# TPSM846C23_template.net
KiCad netlist of a schematic drawn in Altium Designer
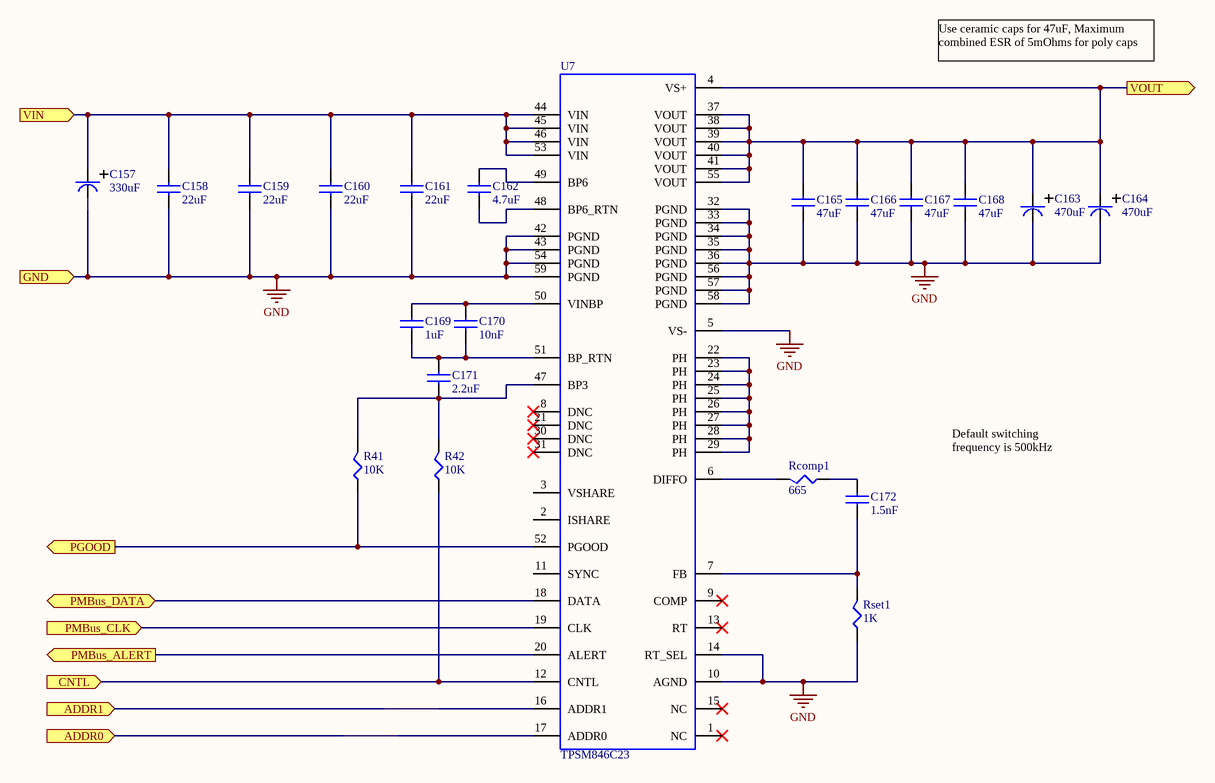
[diagram p0: TPSM846C23_template.SchDoc]

(export (version "E")
  (design (tool "Eeschema 10.0.6"))
  (components
    (comp (ref "C157")
      (value "CAP_POLY_330uF_25V")
      (footprint "CAPAE110103X127M")
      (description "SML-D12U1WT86TR-ND")
      (fields
        (field (name "MANUFACTURER") "Panasonic")
        (field (name "MANUFACTURER PART NUMBER") "25SVF330M")
        (field (name "CAPACITANCE") "330uF")
      )
      (libsource (lib "my_schsymbols") (part "CAP_POLY_330uF_25V"))
    )
    (comp (ref "C158")
      (value "CAP_22uF_1812_25V")
      (footprint "CAPC4532X28N")
      (description "CAP CER 22UF 25V X7R 1812")
      (fields
        (field (name "MANUFACTURER") "TDK")
        (field (name "MANUFACTURER PART NUMBER") "C4532X7R1E226M250KC")
        (field (name "CAPACITANCE") "22uF")
      )
      (libsource (lib "my_schsymbols") (part "CAP_22uF_1812_25V"))
    )
    (comp (ref "C159")
      (value "CAP_22uF_1812_25V")
      (footprint "CAPC4532X28N")
      (description "CAP CER 22UF 25V X7R 1812")
      (fields
        (field (name "MANUFACTURER") "TDK")
        (field (name "MANUFACTURER PART NUMBER") "C4532X7R1E226M250KC")
        (field (name "CAPACITANCE") "22uF")
      )
      (libsource (lib "my_schsymbols") (part "CAP_22uF_1812_25V"))
    )
    (comp (ref "C160")
      (value "CAP_22uF_1812_25V")
      (footprint "CAPC4532X28N")
      (description "CAP CER 22UF 25V X7R 1812")
      (fields
        (field (name "MANUFACTURER") "TDK")
        (field (name "MANUFACTURER PART NUMBER") "C4532X7R1E226M250KC")
        (field (name "CAPACITANCE") "22uF")
      )
      (libsource (lib "my_schsymbols") (part "CAP_22uF_1812_25V"))
    )
    (comp (ref "C161")
      (value "CAP_22uF_1812_25V")
      (footprint "CAPC4532X28N")
      (description "CAP CER 22UF 25V X7R 1812")
      (fields
        (field (name "MANUFACTURER") "TDK")
        (field (name "MANUFACTURER PART NUMBER") "C4532X7R1E226M250KC")
        (field (name "CAPACITANCE") "22uF")
      )
      (libsource (lib "my_schsymbols") (part "CAP_22uF_1812_25V"))
    )
    (comp (ref "C162")
      (value "CAP_4.7uF_0805_25V")
      (footprint "CAPC2012X14N")
      (description "Cap Ceramic 4.7uF 25V X5R 10% SMD 0805 85C Cardboard T/R")
      (fields
        (field (name "MANUFACTURER") "Samsung")
        (field (name "MANUFACTURER PART NUMBER") "CL21A475KACLRNC")
        (field (name "CAPACITANCE") "4.7uF")
      )
      (libsource (lib "CGRA_schlib") (part "CAP_4.7uF_0805_25V"))
    )
    (comp (ref "C163")
      (value "CAP_POLY_470uF_16V")
      (footprint "CAPAE110103X127M")
      (description "CAP POLYMER 470UF 20% 16V SMD")
      (fields
        (field (name "MANUFACTURER") "Panasonic")
        (field (name "MANUFACTURER PART NUMBER") "25SVF330M")
        (field (name "CAPACITANCE") "470uF")
      )
      (libsource (lib "my_schsymbols") (part "CAP_POLY_470uF_16V"))
    )
    (comp (ref "C164")
      (value "CAP_POLY_470uF_16V")
      (footprint "CAPAE110103X127M")
      (description "CAP POLYMER 470UF 20% 16V SMD")
      (fields
        (field (name "MANUFACTURER") "Panasonic")
        (field (name "MANUFACTURER PART NUMBER") "25SVF330M")
        (field (name "CAPACITANCE") "470uF")
      )
      (libsource (lib "my_schsymbols") (part "CAP_POLY_470uF_16V"))
    )
    (comp (ref "C165")
      (value "CAP_47uF_0805_10V")
      (footprint "CAPC2012X14N")
      (description "Cap Ceramic 47uF 10V X5R 20% SMD 0805 85C Embossed T/R")
      (fields
        (field (name "MANUFACTURER") "Murata")
        (field (name "MANUFACTURER PART NUMBER") "GRM21BR61A476ME15L")
        (field (name "CAPACITANCE") "47uF")
      )
      (libsource (lib "CGRA_schlib") (part "CAP_47uF_0805_10V"))
    )
    (comp (ref "C166")
      (value "CAP_47uF_0805_10V")
      (footprint "CAPC2012X14N")
      (description "Cap Ceramic 47uF 10V X5R 20% SMD 0805 85C Embossed T/R")
      (fields
        (field (name "MANUFACTURER") "Murata")
        (field (name "MANUFACTURER PART NUMBER") "GRM21BR61A476ME15L")
        (field (name "CAPACITANCE") "47uF")
      )
      (libsource (lib "CGRA_schlib") (part "CAP_47uF_0805_10V"))
    )
    (comp (ref "C167")
      (value "CAP_47uF_0805_10V")
      (footprint "CAPC2012X14N")
      (description "Cap Ceramic 47uF 10V X5R 20% SMD 0805 85C Embossed T/R")
      (fields
        (field (name "MANUFACTURER") "Murata")
        (field (name "MANUFACTURER PART NUMBER") "GRM21BR61A476ME15L")
        (field (name "CAPACITANCE") "47uF")
      )
      (libsource (lib "CGRA_schlib") (part "CAP_47uF_0805_10V"))
    )
    (comp (ref "C168")
      (value "CAP_47uF_0805_10V")
      (footprint "CAPC2012X14N")
      (description "Cap Ceramic 47uF 10V X5R 20% SMD 0805 85C Embossed T/R")
      (fields
        (field (name "MANUFACTURER") "Murata")
        (field (name "MANUFACTURER PART NUMBER") "GRM21BR61A476ME15L")
        (field (name "CAPACITANCE") "47uF")
      )
      (libsource (lib "CGRA_schlib") (part "CAP_47uF_0805_10V"))
    )
    (comp (ref "C169")
      (value "CAP_1uF_0805_25V")
      (footprint "CAPC2012X14N")
      (description "CAP CER 1UF 25V X7R 0805")
      (fields
        (field (name "MANUFACTURER") "Yageo")
        (field (name "MANUFACTURER PART NUMBER") "CC0805KKX7R8BB105")
        (field (name "CAPACITANCE") "1uF")
      )
      (libsource (lib "CGRA_schlib") (part "CAP_1uF_0805_25V"))
    )
    (comp (ref "C170")
      (value "CAP_10nF_0402_25V")
      (footprint "CAPC1005X06N")
      (description "CAP CER 10000PF 50V X7R 0402")
      (fields
        (field (name "MANUFACTURER") "Murata")
        (field (name "MANUFACTURER PART NUMBER") "GCM155R71H103KA55D")
        (field (name "CAPACITANCE") "10nF")
      )
      (libsource (lib "CGRA_schlib") (part "CAP_10nF_0402_25V"))
    )
    (comp (ref "C171")
      (value "CAP_2.2uF_0402_25V")
      (footprint "CAPC1005X06N")
      (description "Multilayer Ceramic Capacitors MLCC - SMD/SMT 0402 2.2uF 25volts *Derate Voltage/Temp")
      (fields
        (field (name "MANUFACTURER") "Murata")
        (field (name "MANUFACTURER PART NUMBER") "GRM155R61E225ME15D")
        (field (name "CAPACITANCE") "2.2uF")
      )
      (libsource (lib "CGRA_schlib") (part "CAP_2.2uF_0402_25V"))
    )
    (comp (ref "C172")
      (value "CAP_1500pF_0201_25V")
      (footprint "CAPC0603X02N")
      (description "Multilayer Ceramic Capacitors MLCC - SMD/SMT 0.0015uF 25Volts 10%")
      (fields
        (field (name "MANUFACTURER") "Murata")
        (field (name "MANUFACTURER PART NUMBER") "GCM033R71E152KA03D")
        (field (name "CAPACITANCE") "1.5nF")
      )
      (libsource (lib "CGRA_schlib") (part "CAP_1500pF_0201_25V"))
    )
    (comp (ref "R41")
      (value "RES_10K_0603")
      (footprint "RESC1608X06N")
      (description "RES SMD 10K OHM 1% 1/4W 0603")
      (fields
        (field (name "MANUFACTURER") "Rohm")
        (field (name "MANUFACTURER PART NUMBER") "ESR03EZPF1002")
        (field (name "RESISTANCE") "10K")
      )
      (libsource (lib "CGRA_schlib") (part "RES_10K_0603"))
    )
    (comp (ref "R42")
      (value "RES_10K_0603")
      (footprint "RESC1608X06N")
      (description "RES SMD 10K OHM 1% 1/4W 0603")
      (fields
        (field (name "MANUFACTURER") "Rohm")
        (field (name "MANUFACTURER PART NUMBER") "ESR03EZPF1002")
        (field (name "RESISTANCE") "10K")
      )
      (libsource (lib "CGRA_schlib") (part "RES_10K_0603"))
    )
    (comp (ref "Rcomp1")
      (value "RES_665_0603")
      (footprint "RESC1608X06N")
      (description "RESISTOR, 665R, 0603, 0.1%, 0.1W")
      (fields
        (field (name "MANUFACTURER") "Panasonic")
        (field (name "MANUFACTURER PART NUMBER") "ERA3AEB6650V")
        (field (name "RESISTANCE") "665")
      )
      (libsource (lib "CGRA_schlib") (part "RES_665_0603"))
    )
    (comp (ref "Rset1")
      (value "RES_1K_0603")
      (footprint "RESC1608X06N")
      (description "RES SMD 1K OHM 5% 1/4W 0603")
      (fields
        (field (name "MANUFACTURER") "Rohm")
        (field (name "MANUFACTURER PART NUMBER") "ESR03EZPJ102")
        (field (name "RESISTANCE") "1K")
      )
      (libsource (lib "CGRA_schlib") (part "RES_1K_0603"))
    )
    (comp (ref "U7")
      (value "TPSM846C23")
      (footprint "QFM-59")
      (description "Non-Isolated PoL Module DC DC Converter 1 Output 0.35 ~ 2V 35A 4.5V - 15V Input")
      (fields
        (field (name "MANUFACTURER") "Texas Instruments")
        (field (name "MANUFACTURER PART NUMBER") "TPSM846C23MOLR")
      )
      (libsource (lib "my_schsymbols") (part "TPSM846C23"))
    )
  )
  (nets
    (net (code "1") (name "/ADDR0") (class "Default")
      (node (ref "U7") (pin "17") (pinfunction "ADDR0_17") (pintype "passive"))
    )
    (net (code "2") (name "/ADDR1") (class "Default")
      (node (ref "U7") (pin "16") (pinfunction "ADDR1_16") (pintype "passive"))
    )
    (net (code "3") (name "/CNTL") (class "Default")
      (node (ref "R42") (pin "2") (pinfunction "2_2") (pintype "passive"))
      (node (ref "U7") (pin "12") (pinfunction "CNTL_12") (pintype "passive"))
    )
    (net (code "4") (name "/PGOOD") (class "Default")
      (node (ref "R41") (pin "2") (pinfunction "2_2") (pintype "passive"))
      (node (ref "U7") (pin "52") (pinfunction "PGOOD_52") (pintype "passive"))
    )
    (net (code "5") (name "/PMBus_ALERT") (class "Default")
      (node (ref "U7") (pin "20") (pinfunction "ALERT_20") (pintype "passive"))
    )
    (net (code "6") (name "/PMBus_CLK") (class "Default")
      (node (ref "U7") (pin "19") (pinfunction "CLK_19") (pintype "passive"))
    )
    (net (code "7") (name "/PMBus_DATA") (class "Default")
      (node (ref "U7") (pin "18") (pinfunction "DATA_18") (pintype "passive"))
    )
    (net (code "8") (name "/VIN") (class "Default")
      (node (ref "C157") (pin "1") (pinfunction "1_1") (pintype "passive"))
      (node (ref "C158") (pin "1") (pintype "passive"))
      (node (ref "C159") (pin "1") (pintype "passive"))
      (node (ref "C160") (pin "1") (pintype "passive"))
      (node (ref "C161") (pin "1") (pintype "passive"))
      (node (ref "U7") (pin "44") (pinfunction "VIN_44") (pintype "passive"))
      (node (ref "U7") (pin "45") (pinfunction "VIN_45") (pintype "passive"))
      (node (ref "U7") (pin "46") (pinfunction "VIN_46") (pintype "passive"))
      (node (ref "U7") (pin "53") (pinfunction "VIN_53") (pintype "passive"))
    )
    (net (code "9") (name "/VOUT") (class "Default")
      (node (ref "C163") (pin "1") (pinfunction "1_1") (pintype "passive"))
      (node (ref "C164") (pin "1") (pinfunction "1_1") (pintype "passive"))
      (node (ref "C165") (pin "1") (pintype "passive"))
      (node (ref "C166") (pin "1") (pintype "passive"))
      (node (ref "C167") (pin "1") (pintype "passive"))
      (node (ref "C168") (pin "1") (pintype "passive"))
      (node (ref "U7") (pin "37") (pinfunction "VOUT_37") (pintype "passive"))
      (node (ref "U7") (pin "38") (pinfunction "VOUT_38") (pintype "passive"))
      (node (ref "U7") (pin "39") (pinfunction "VOUT_39") (pintype "passive"))
      (node (ref "U7") (pin "4") (pinfunction "VS+_4") (pintype "passive"))
      (node (ref "U7") (pin "40") (pinfunction "VOUT_40") (pintype "passive"))
      (node (ref "U7") (pin "41") (pinfunction "VOUT_41") (pintype "passive"))
      (node (ref "U7") (pin "55") (pinfunction "VOUT_55") (pintype "passive"))
    )
    (net (code "10") (name "GND") (class "Default")
      (node (ref "C157") (pin "2") (pinfunction "2_2") (pintype "passive"))
      (node (ref "C158") (pin "2") (pinfunction "2_2") (pintype "passive"))
      (node (ref "C159") (pin "2") (pinfunction "2_2") (pintype "passive"))
      (node (ref "C160") (pin "2") (pinfunction "2_2") (pintype "passive"))
      (node (ref "C161") (pin "2") (pinfunction "2_2") (pintype "passive"))
      (node (ref "C163") (pin "2") (pinfunction "2_2") (pintype "passive"))
      (node (ref "C164") (pin "2") (pinfunction "2_2") (pintype "passive"))
      (node (ref "C165") (pin "2") (pinfunction "2_2") (pintype "passive"))
      (node (ref "C166") (pin "2") (pinfunction "2_2") (pintype "passive"))
      (node (ref "C167") (pin "2") (pinfunction "2_2") (pintype "passive"))
      (node (ref "C168") (pin "2") (pinfunction "2_2") (pintype "passive"))
      (node (ref "Rset1") (pin "2") (pinfunction "2_2") (pintype "passive"))
      (node (ref "U7") (pin "10") (pinfunction "AGND_10") (pintype "passive"))
      (node (ref "U7") (pin "14") (pinfunction "RT_SEL_14") (pintype "passive"))
      (node (ref "U7") (pin "32") (pinfunction "PGND_32") (pintype "passive"))
      (node (ref "U7") (pin "33") (pinfunction "PGND_33") (pintype "passive"))
      (node (ref "U7") (pin "34") (pinfunction "PGND_34") (pintype "passive"))
      (node (ref "U7") (pin "35") (pinfunction "PGND_35") (pintype "passive"))
      (node (ref "U7") (pin "36") (pinfunction "PGND_36") (pintype "passive"))
      (node (ref "U7") (pin "42") (pinfunction "PGND_42") (pintype "passive"))
      (node (ref "U7") (pin "43") (pinfunction "PGND_43") (pintype "passive"))
      (node (ref "U7") (pin "5") (pinfunction "VS-_5") (pintype "passive"))
      (node (ref "U7") (pin "54") (pinfunction "PGND_54") (pintype "passive"))
      (node (ref "U7") (pin "56") (pinfunction "PGND_56") (pintype "passive"))
      (node (ref "U7") (pin "57") (pinfunction "PGND_57") (pintype "passive"))
      (node (ref "U7") (pin "58") (pinfunction "PGND_58") (pintype "passive"))
      (node (ref "U7") (pin "59") (pinfunction "PGND_59") (pintype "passive"))
    )
    (net (code "11") (name "Net-(C172-Pad1)") (class "Default")
      (node (ref "C172") (pin "1") (pintype "passive"))
      (node (ref "Rcomp1") (pin "2") (pinfunction "2_2") (pintype "passive"))
    )
    (net (code "12") (name "Net-(U7-BP3)") (class "Default")
      (node (ref "C171") (pin "2") (pinfunction "2_2") (pintype "passive"))
      (node (ref "R41") (pin "1") (pintype "passive"))
      (node (ref "R42") (pin "1") (pintype "passive"))
      (node (ref "U7") (pin "47") (pinfunction "BP3_47") (pintype "passive"))
    )
    (net (code "13") (name "Net-(U7-BP6)") (class "Default")
      (node (ref "C162") (pin "1") (pintype "passive"))
      (node (ref "U7") (pin "49") (pinfunction "BP6_49") (pintype "passive"))
    )
    (net (code "14") (name "Net-(U7-BP6_RTN)") (class "Default")
      (node (ref "C162") (pin "2") (pinfunction "2_2") (pintype "passive"))
      (node (ref "U7") (pin "48") (pinfunction "BP6_RTN_48") (pintype "passive"))
    )
    (net (code "15") (name "Net-(U7-BP_RTN)") (class "Default")
      (node (ref "C169") (pin "2") (pinfunction "2_2") (pintype "passive"))
      (node (ref "C170") (pin "2") (pinfunction "2_2") (pintype "passive"))
      (node (ref "C171") (pin "1") (pintype "passive"))
      (node (ref "U7") (pin "51") (pinfunction "BP_RTN_51") (pintype "passive"))
    )
    (net (code "16") (name "Net-(U7-DIFFO)") (class "Default")
      (node (ref "Rcomp1") (pin "1") (pintype "passive"))
      (node (ref "U7") (pin "6") (pinfunction "DIFFO_6") (pintype "passive"))
    )
    (net (code "17") (name "Net-(U7-FB)") (class "Default")
      (node (ref "C172") (pin "2") (pinfunction "2_2") (pintype "passive"))
      (node (ref "Rset1") (pin "1") (pintype "passive"))
      (node (ref "U7") (pin "7") (pinfunction "FB_7") (pintype "passive"))
    )
    (net (code "18") (name "Net-(U7-PH-Pad22)") (class "Default")
      (node (ref "U7") (pin "22") (pinfunction "PH_22") (pintype "passive"))
      (node (ref "U7") (pin "23") (pinfunction "PH_23") (pintype "passive"))
      (node (ref "U7") (pin "24") (pinfunction "PH_24") (pintype "passive"))
      (node (ref "U7") (pin "25") (pinfunction "PH_25") (pintype "passive"))
      (node (ref "U7") (pin "26") (pinfunction "PH_26") (pintype "passive"))
      (node (ref "U7") (pin "27") (pinfunction "PH_27") (pintype "passive"))
      (node (ref "U7") (pin "28") (pinfunction "PH_28") (pintype "passive"))
      (node (ref "U7") (pin "29") (pinfunction "PH_29") (pintype "passive"))
    )
    (net (code "19") (name "Net-(U7-VINBP)") (class "Default")
      (node (ref "C169") (pin "1") (pintype "passive"))
      (node (ref "C170") (pin "1") (pintype "passive"))
      (node (ref "U7") (pin "50") (pinfunction "VINBP_50") (pintype "passive"))
    )
    (net (code "20") (name "unconnected-(U7-COMP-Pad9)") (class "Default")
      (node (ref "U7") (pin "9") (pinfunction "COMP_9") (pintype "passive+no_connect"))
    )
    (net (code "21") (name "unconnected-(U7-DNC-Pad8)") (class "Default")
      (node (ref "U7") (pin "8") (pinfunction "DNC_8") (pintype "passive+no_connect"))
    )
    (net (code "22") (name "unconnected-(U7-DNC-Pad21)") (class "Default")
      (node (ref "U7") (pin "21") (pinfunction "DNC_21") (pintype "passive+no_connect"))
    )
    (net (code "23") (name "unconnected-(U7-DNC-Pad30)") (class "Default")
      (node (ref "U7") (pin "30") (pinfunction "DNC_30") (pintype "passive+no_connect"))
    )
    (net (code "24") (name "unconnected-(U7-DNC-Pad31)") (class "Default")
      (node (ref "U7") (pin "31") (pinfunction "DNC_31") (pintype "passive+no_connect"))
    )
    (net (code "25") (name "unconnected-(U7-ISHARE-Pad2)") (class "Default")
      (node (ref "U7") (pin "2") (pinfunction "ISHARE_2") (pintype "passive"))
    )
    (net (code "26") (name "unconnected-(U7-NC-Pad1)") (class "Default")
      (node (ref "U7") (pin "1") (pinfunction "NC_1") (pintype "passive+no_connect"))
    )
    (net (code "27") (name "unconnected-(U7-NC-Pad15)") (class "Default")
      (node (ref "U7") (pin "15") (pinfunction "NC_15") (pintype "passive+no_connect"))
    )
    (net (code "28") (name "unconnected-(U7-RT-Pad13)") (class "Default")
      (node (ref "U7") (pin "13") (pinfunction "RT_13") (pintype "passive+no_connect"))
    )
    (net (code "29") (name "unconnected-(U7-SYNC-Pad11)") (class "Default")
      (node (ref "U7") (pin "11") (pinfunction "SYNC_11") (pintype "passive"))
    )
    (net (code "30") (name "unconnected-(U7-VSHARE-Pad3)") (class "Default")
      (node (ref "U7") (pin "3") (pinfunction "VSHARE_3") (pintype "passive"))
    )
  )
)
